# MomoinololuM3_Rev1_1.net
KiCad netlist of a schematic drawn in EAGLE
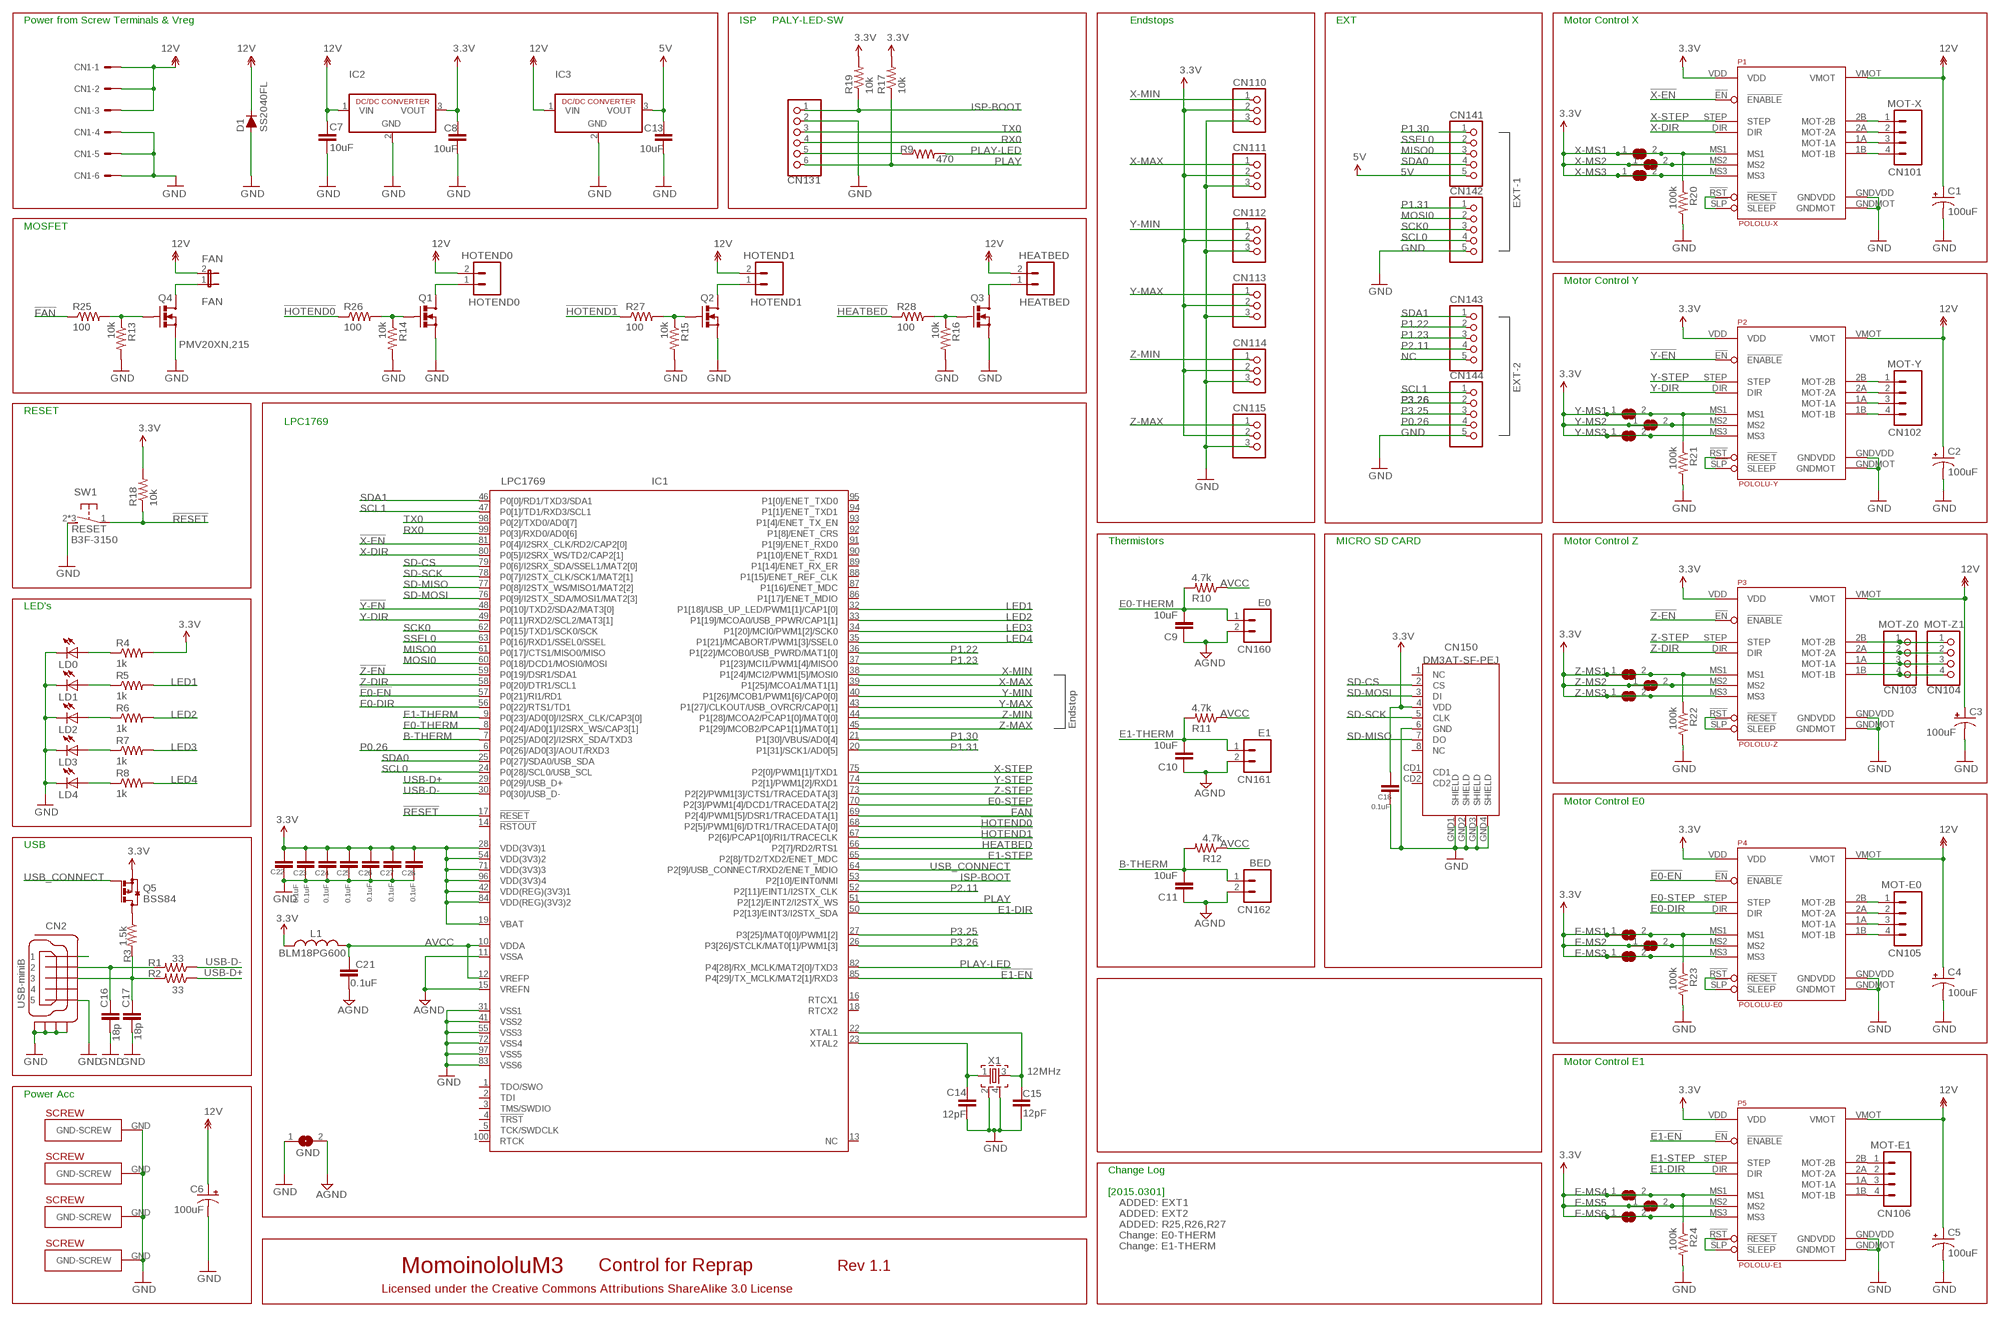
[diagram p0: schematic, sheet 1]

(export (version "E")
  (design (tool "Eeschema 10.0.6"))
  (components
    (comp (ref "C1")
      (value "100uF")
      (footprint "eagle-import:UD-6,3X7,7_NICHICON")
      (libsource (lib "eagle-import") (part "CPOL-USUD-6,3X7,7"))
    )
    (comp (ref "C2")
      (value "100uF")
      (footprint "eagle-import:UD-6,3X7,7_NICHICON")
      (libsource (lib "eagle-import") (part "CPOL-USUD-6,3X7,7"))
    )
    (comp (ref "C3")
      (value "100uF")
      (footprint "eagle-import:UD-6,3X7,7_NICHICON")
      (libsource (lib "eagle-import") (part "CPOL-USUD-6,3X7,7"))
    )
    (comp (ref "C4")
      (value "100uF")
      (footprint "eagle-import:UD-6,3X7,7_NICHICON")
      (libsource (lib "eagle-import") (part "CPOL-USUD-6,3X7,7"))
    )
    (comp (ref "C5")
      (value "100uF")
      (footprint "eagle-import:UD-6,3X7,7_NICHICON")
      (libsource (lib "eagle-import") (part "CPOL-USUD-6,3X7,7"))
    )
    (comp (ref "C6")
      (value "100uF")
      (footprint "eagle-import:UD-6,3X7,7_NICHICON")
      (libsource (lib "eagle-import") (part "CPOL-USUD-6,3X7,7"))
    )
    (comp (ref "C7")
      (value "10uF")
      (footprint "eagle-import:RCL_C1206K")
      (libsource (lib "eagle-import") (part "RCL_C-EUC1206K"))
    )
    (comp (ref "C8")
      (value "10uF")
      (footprint "eagle-import:RCL_C1206K")
      (libsource (lib "eagle-import") (part "RCL_C-EUC1206K"))
    )
    (comp (ref "C9")
      (value "10uF")
      (footprint "eagle-import:RCL_C1206K")
      (libsource (lib "eagle-import") (part "RCL_C-EUC1206K"))
    )
    (comp (ref "C10")
      (value "10uF")
      (footprint "eagle-import:RCL_C1206K")
      (libsource (lib "eagle-import") (part "RCL_C-EUC1206K"))
    )
    (comp (ref "C11")
      (value "10uF")
      (footprint "eagle-import:RCL_C1206K")
      (libsource (lib "eagle-import") (part "RCL_C-EUC1206K"))
    )
    (comp (ref "C13")
      (value "10uF")
      (footprint "eagle-import:RCL_C1206K")
      (libsource (lib "eagle-import") (part "RCL_C-EUC1206K"))
    )
    (comp (ref "C14")
      (value "12pF")
      (footprint "eagle-import:C0603")
      (libsource (lib "eagle-import") (part "C-EUC0603"))
    )
    (comp (ref "C15")
      (value "12pF")
      (footprint "eagle-import:C0603")
      (libsource (lib "eagle-import") (part "C-EUC0603"))
    )
    (comp (ref "C16")
      (value "18p")
      (footprint "eagle-import:C0603")
      (libsource (lib "eagle-import") (part "C-EUC0603"))
    )
    (comp (ref "C17")
      (value "18p")
      (footprint "eagle-import:C0603")
      (libsource (lib "eagle-import") (part "C-EUC0603"))
    )
    (comp (ref "C18")
      (value "0.1uF")
      (footprint "eagle-import:C0603")
      (libsource (lib "eagle-import") (part "C-EUC0603"))
    )
    (comp (ref "C21")
      (value "0.1uF")
      (footprint "eagle-import:C0603")
      (libsource (lib "eagle-import") (part "C-EUC0603"))
    )
    (comp (ref "C22")
      (value "0.1uF")
      (footprint "eagle-import:C0603")
      (libsource (lib "eagle-import") (part "C-EUC0603"))
    )
    (comp (ref "C23")
      (value "0.1uF")
      (footprint "eagle-import:C0603")
      (libsource (lib "eagle-import") (part "C-EUC0603"))
    )
    (comp (ref "C24")
      (value "0.1uF")
      (footprint "eagle-import:C0603")
      (libsource (lib "eagle-import") (part "C-EUC0603"))
    )
    (comp (ref "C25")
      (value "0.1uF")
      (footprint "eagle-import:C0603")
      (libsource (lib "eagle-import") (part "C-EUC0603"))
    )
    (comp (ref "C26")
      (value "0.1uF")
      (footprint "eagle-import:C0603")
      (libsource (lib "eagle-import") (part "C-EUC0603"))
    )
    (comp (ref "C27")
      (value "0.1uF")
      (footprint "eagle-import:C0603")
      (libsource (lib "eagle-import") (part "C-EUC0603"))
    )
    (comp (ref "C28")
      (value "0.1uF")
      (footprint "eagle-import:C0603")
      (libsource (lib "eagle-import") (part "C-EUC0603"))
    )
    (comp (ref "CN1")
      (value "556X-6H")
      (footprint "eagle-import:5569-6")
      (libsource (lib "eagle-import") (part "556X-6H"))
    )
    (comp (ref "CN2")
      (value "USB-miniB")
      (footprint "eagle-import:CON-HIROSE_UX60A-MB-5ST")
      (libsource (lib "eagle-import") (part "CON-HIROSE_MINI-USB-SHIELD-UX60A-MB-5ST"))
    )
    (comp (ref "CN101")
      (value "MOT-X")
      (footprint "eagle-import:SPARKFUN_MOLEX-1X4")
      (libsource (lib "eagle-import") (part "SPARKFUN_M04POLAR"))
    )
    (comp (ref "CN102")
      (value "MOT-Y")
      (footprint "eagle-import:SPARKFUN_MOLEX-1X4")
      (libsource (lib "eagle-import") (part "SPARKFUN_M04POLAR"))
    )
    (comp (ref "CN103")
      (value "MOT-Z0")
      (footprint "eagle-import:1X04")
      (libsource (lib "eagle-import") (part "PINHD-1X4"))
    )
    (comp (ref "CN104")
      (value "MOT-Z1")
      (footprint "eagle-import:1X04")
      (libsource (lib "eagle-import") (part "PINHD-1X4"))
    )
    (comp (ref "CN105")
      (value "MOT-E0")
      (footprint "eagle-import:SPARKFUN_MOLEX-1X4")
      (libsource (lib "eagle-import") (part "SPARKFUN_M04POLAR"))
    )
    (comp (ref "CN106")
      (value "MOT-E1")
      (footprint "eagle-import:SPARKFUN_MOLEX-1X4")
      (libsource (lib "eagle-import") (part "SPARKFUN_M04POLAR"))
    )
    (comp (ref "CN110")
      (value "PINHD-1X3")
      (footprint "eagle-import:1X03")
      (libsource (lib "eagle-import") (part "PINHD-1X3"))
    )
    (comp (ref "CN111")
      (value "PINHD-1X3")
      (footprint "eagle-import:1X03")
      (libsource (lib "eagle-import") (part "PINHD-1X3"))
    )
    (comp (ref "CN112")
      (value "PINHD-1X3")
      (footprint "eagle-import:1X03")
      (libsource (lib "eagle-import") (part "PINHD-1X3"))
    )
    (comp (ref "CN113")
      (value "PINHD-1X3")
      (footprint "eagle-import:1X03")
      (libsource (lib "eagle-import") (part "PINHD-1X3"))
    )
    (comp (ref "CN114")
      (value "PINHD-1X3")
      (footprint "eagle-import:1X03")
      (libsource (lib "eagle-import") (part "PINHD-1X3"))
    )
    (comp (ref "CN115")
      (value "PINHD-1X3")
      (footprint "eagle-import:1X03")
      (libsource (lib "eagle-import") (part "PINHD-1X3"))
    )
    (comp (ref "CN131")
      (value "PINHD-1X6")
      (footprint "eagle-import:1X06")
      (libsource (lib "eagle-import") (part "PINHD-1X6"))
    )
    (comp (ref "CN141")
      (value "PINHD-1X5")
      (footprint "eagle-import:1X05")
      (libsource (lib "eagle-import") (part "PINHD-1X5"))
    )
    (comp (ref "CN142")
      (value "PINHD-1X5")
      (footprint "eagle-import:1X05")
      (libsource (lib "eagle-import") (part "PINHD-1X5"))
    )
    (comp (ref "CN143")
      (value "PINHD-1X5")
      (footprint "eagle-import:1X05")
      (libsource (lib "eagle-import") (part "PINHD-1X5"))
    )
    (comp (ref "CN144")
      (value "PINHD-1X5")
      (footprint "eagle-import:1X05")
      (libsource (lib "eagle-import") (part "PINHD-1X5"))
    )
    (comp (ref "CN150")
      (value "DM3AT-SF-PEJ")
      (footprint "eagle-import:DM3AT-SF-PEJ")
      (libsource (lib "eagle-import") (part "DM3AT-SF-PEJ"))
    )
    (comp (ref "CN160")
      (value "E0")
      (footprint "eagle-import:SPARKFUN_1X02")
      (libsource (lib "eagle-import") (part "momoinololuM3_SPARKFUN_M02PTH"))
    )
    (comp (ref "CN161")
      (value "E1")
      (footprint "eagle-import:SPARKFUN_1X02")
      (libsource (lib "eagle-import") (part "momoinololuM3_SPARKFUN_M02PTH"))
    )
    (comp (ref "CN162")
      (value "BED")
      (footprint "eagle-import:SPARKFUN_1X02")
      (libsource (lib "eagle-import") (part "momoinololuM3_SPARKFUN_M02PTH"))
    )
    (comp (ref "D1")
      (value "SS2040FL")
      (footprint "eagle-import:SEMICON-SMD-IPC_SOD123")
      (libsource (lib "eagle-import") (part "SEMICON-SMD-IPC_D-FILL-SOD123"))
    )
    (comp (ref "E-MS1")
      (value "SJ")
      (footprint "eagle-import:SJ")
      (libsource (lib "eagle-import") (part "SJ"))
    )
    (comp (ref "E-MS2")
      (value "SJ")
      (footprint "eagle-import:SJ")
      (libsource (lib "eagle-import") (part "SJ"))
    )
    (comp (ref "E-MS3")
      (value "SJ")
      (footprint "eagle-import:SJ")
      (libsource (lib "eagle-import") (part "SJ"))
    )
    (comp (ref "E-MS4")
      (value "SJ")
      (footprint "eagle-import:SJ")
      (libsource (lib "eagle-import") (part "SJ"))
    )
    (comp (ref "E-MS5")
      (value "SJ")
      (footprint "eagle-import:SJ")
      (libsource (lib "eagle-import") (part "SJ"))
    )
    (comp (ref "E-MS6")
      (value "SJ")
      (footprint "eagle-import:SJ")
      (libsource (lib "eagle-import") (part "SJ"))
    )
    (comp (ref "FAN")
      (value "FAN")
      (footprint "eagle-import:SPARKFUN_1X02")
      (libsource (lib "eagle-import") (part "SPARKFUN_JUMPER-2PTH"))
    )
    (comp (ref "GND") (value "SJ") (footprint "eagle-import:SJ") (libsource (lib "eagle-import") (part "SJ")))
    (comp (ref "HEATBED")
      (value "HEATBED")
      (footprint "eagle-import:SCREWTERMINAL-5.08MM-2")
      (libsource (lib "eagle-import") (part "SPARKFUN_M025.08MM"))
    )
    (comp (ref "HOLE1")
      (value "PLATED-SCREW")
      (footprint "eagle-import:PLATEDSCREW")
      (libsource (lib "eagle-import") (part "PLATED-SCREW"))
    )
    (comp (ref "HOLE2")
      (value "PLATED-SCREW")
      (footprint "eagle-import:PLATEDSCREW")
      (libsource (lib "eagle-import") (part "PLATED-SCREW"))
    )
    (comp (ref "HOLE3")
      (value "PLATED-SCREW")
      (footprint "eagle-import:PLATEDSCREW")
      (libsource (lib "eagle-import") (part "PLATED-SCREW"))
    )
    (comp (ref "HOLE4")
      (value "PLATED-SCREW")
      (footprint "eagle-import:PLATEDSCREW")
      (libsource (lib "eagle-import") (part "PLATED-SCREW"))
    )
    (comp (ref "HOTEND0")
      (value "HOTEND0")
      (footprint "eagle-import:SCREWTERMINAL-5.08MM-2")
      (libsource (lib "eagle-import") (part "SPARKFUN_M025.08MM"))
    )
    (comp (ref "HOTEND1")
      (value "HOTEND1")
      (footprint "eagle-import:SCREWTERMINAL-5.08MM-2")
      (libsource (lib "eagle-import") (part "SPARKFUN_M025.08MM"))
    )
    (comp (ref "IC1")
      (value "LPC1769")
      (footprint "eagle-import:LQFP100-14X14")
      (libsource (lib "eagle-import") (part "LPC1768"))
    )
    (comp (ref "IC2")
      (value "R-78E3.3-0.5")
      (footprint "eagle-import:SIP3")
      (libsource (lib "eagle-import") (part "R-78C-1.03.3"))
    )
    (comp (ref "IC3")
      (value "R-78E5.0-0.5")
      (footprint "eagle-import:SIP3")
      (libsource (lib "eagle-import") (part "R-78C-1.03.3"))
    )
    (comp (ref "L1")
      (value "BLM18PG600")
      (footprint "eagle-import:L2012C")
      (libsource (lib "eagle-import") (part "L-USL2012C"))
    )
    (comp (ref "LD0")
      (value "LEDSML0805")
      (footprint "eagle-import:SML0805")
      (libsource (lib "eagle-import") (part "LEDSML0805"))
    )
    (comp (ref "LD1")
      (value "LEDSML0805")
      (footprint "eagle-import:SML0805")
      (libsource (lib "eagle-import") (part "LEDSML0805"))
    )
    (comp (ref "LD2")
      (value "LEDSML0805")
      (footprint "eagle-import:SML0805")
      (libsource (lib "eagle-import") (part "LEDSML0805"))
    )
    (comp (ref "LD3")
      (value "LEDSML0805")
      (footprint "eagle-import:SML0805")
      (libsource (lib "eagle-import") (part "LEDSML0805"))
    )
    (comp (ref "LD4")
      (value "LEDSML0805")
      (footprint "eagle-import:SML0805")
      (libsource (lib "eagle-import") (part "LEDSML0805"))
    )
    (comp (ref "P1")
      (value "POLOLU-X")
      (footprint "eagle-import:POLOLU-ALLEGRO_POLOLU-ALLEGRO-PTH")
      (libsource (lib "eagle-import") (part "POLOLU-ALLEGRO_POLOLU-ALLEGRO"))
    )
    (comp (ref "P2")
      (value "POLOLU-Y")
      (footprint "eagle-import:POLOLU-ALLEGRO_POLOLU-ALLEGRO-PTH")
      (libsource (lib "eagle-import") (part "POLOLU-ALLEGRO_POLOLU-ALLEGRO"))
    )
    (comp (ref "P3")
      (value "POLOLU-Z")
      (footprint "eagle-import:POLOLU-ALLEGRO_POLOLU-ALLEGRO-PTH")
      (libsource (lib "eagle-import") (part "POLOLU-ALLEGRO_POLOLU-ALLEGRO"))
    )
    (comp (ref "P4")
      (value "POLOLU-E0")
      (footprint "eagle-import:POLOLU-ALLEGRO_POLOLU-ALLEGRO-PTH")
      (libsource (lib "eagle-import") (part "POLOLU-ALLEGRO_POLOLU-ALLEGRO"))
    )
    (comp (ref "P5")
      (value "POLOLU-E1")
      (footprint "eagle-import:POLOLU-ALLEGRO_POLOLU-ALLEGRO-PTH")
      (libsource (lib "eagle-import") (part "POLOLU-ALLEGRO_POLOLU-ALLEGRO"))
    )
    (comp (ref "Q1")
      (value "PSMN038-100YLX")
      (footprint "eagle-import:SOT669")
      (libsource (lib "eagle-import") (part "SPARKFUN_MOSFET-NCHANNELSOT669"))
    )
    (comp (ref "Q2")
      (value "PSMN038-100YLX")
      (footprint "eagle-import:SOT669")
      (libsource (lib "eagle-import") (part "SPARKFUN_MOSFET-NCHANNELSOT669"))
    )
    (comp (ref "Q3")
      (value "PSMN038-100YLX")
      (footprint "eagle-import:SOT669")
      (libsource (lib "eagle-import") (part "SPARKFUN_MOSFET-NCHANNELSOT669"))
    )
    (comp (ref "Q4")
      (value "PMV20XN,215")
      (footprint "eagle-import:SPARKFUN_SOT23-3")
      (libsource (lib "eagle-import") (part "momoinololuM3_SPARKFUN_MOSFET-NCHANNELSMD"))
    )
    (comp (ref "Q5")
      (value "BSS84")
      (footprint "eagle-import:SOT23")
      (libsource (lib "eagle-import") (part "BSS84"))
    )
    (comp (ref "R1")
      (value "33")
      (footprint "eagle-import:R0603")
      (libsource (lib "eagle-import") (part "R-US_R0603"))
    )
    (comp (ref "R2")
      (value "33")
      (footprint "eagle-import:R0603")
      (libsource (lib "eagle-import") (part "R-US_R0603"))
    )
    (comp (ref "R3")
      (value "1.5k")
      (footprint "eagle-import:R0603")
      (libsource (lib "eagle-import") (part "R-US_R0603"))
    )
    (comp (ref "R4")
      (value "1k")
      (footprint "eagle-import:R0603")
      (libsource (lib "eagle-import") (part "R-US_R0603"))
    )
    (comp (ref "R5")
      (value "1k")
      (footprint "eagle-import:R0603")
      (libsource (lib "eagle-import") (part "R-US_R0603"))
    )
    (comp (ref "R6")
      (value "1k")
      (footprint "eagle-import:R0603")
      (libsource (lib "eagle-import") (part "R-US_R0603"))
    )
    (comp (ref "R7")
      (value "1k")
      (footprint "eagle-import:R0603")
      (libsource (lib "eagle-import") (part "R-US_R0603"))
    )
    (comp (ref "R8")
      (value "1k")
      (footprint "eagle-import:R0603")
      (libsource (lib "eagle-import") (part "R-US_R0603"))
    )
    (comp (ref "R9")
      (value "470")
      (footprint "eagle-import:R0603")
      (libsource (lib "eagle-import") (part "R-US_R0603"))
    )
    (comp (ref "R10")
      (value "4.7k")
      (footprint "eagle-import:R0603")
      (libsource (lib "eagle-import") (part "R-US_R0603"))
    )
    (comp (ref "R11")
      (value "4.7k")
      (footprint "eagle-import:R0603")
      (libsource (lib "eagle-import") (part "R-US_R0603"))
    )
    (comp (ref "R12")
      (value "4.7k")
      (footprint "eagle-import:R0603")
      (libsource (lib "eagle-import") (part "R-US_R0603"))
    )
    (comp (ref "R13")
      (value "10k")
      (footprint "eagle-import:R0603")
      (libsource (lib "eagle-import") (part "R-US_R0603"))
    )
    (comp (ref "R14")
      (value "10k")
      (footprint "eagle-import:R0603")
      (libsource (lib "eagle-import") (part "R-US_R0603"))
    )
    (comp (ref "R15")
      (value "10k")
      (footprint "eagle-import:R0603")
      (libsource (lib "eagle-import") (part "R-US_R0603"))
    )
    (comp (ref "R16")
      (value "10k")
      (footprint "eagle-import:R0603")
      (libsource (lib "eagle-import") (part "R-US_R0603"))
    )
    (comp (ref "R17")
      (value "10k")
      (footprint "eagle-import:R0603")
      (libsource (lib "eagle-import") (part "R-US_R0603"))
    )
    (comp (ref "R18")
      (value "10k")
      (footprint "eagle-import:R0603")
      (libsource (lib "eagle-import") (part "R-US_R0603"))
    )
    (comp (ref "R19")
      (value "10k")
      (footprint "eagle-import:R0603")
      (libsource (lib "eagle-import") (part "R-US_R0603"))
    )
    (comp (ref "R20")
      (value "100k")
      (footprint "eagle-import:R0603")
      (libsource (lib "eagle-import") (part "R-US_R0603"))
    )
    (comp (ref "R21")
      (value "100k")
      (footprint "eagle-import:R0603")
      (libsource (lib "eagle-import") (part "R-US_R0603"))
    )
    (comp (ref "R22")
      (value "100k")
      (footprint "eagle-import:R0603")
      (libsource (lib "eagle-import") (part "R-US_R0603"))
    )
    (comp (ref "R23")
      (value "100k")
      (footprint "eagle-import:R0603")
      (libsource (lib "eagle-import") (part "R-US_R0603"))
    )
    (comp (ref "R24")
      (value "100k")
      (footprint "eagle-import:R0603")
      (libsource (lib "eagle-import") (part "R-US_R0603"))
    )
    (comp (ref "R25")
      (value "100")
      (footprint "eagle-import:R0603")
      (libsource (lib "eagle-import") (part "R-US_R0603"))
    )
    (comp (ref "R26")
      (value "100")
      (footprint "eagle-import:R0603")
      (libsource (lib "eagle-import") (part "R-US_R0603"))
    )
    (comp (ref "R27")
      (value "100")
      (footprint "eagle-import:R0603")
      (libsource (lib "eagle-import") (part "R-US_R0603"))
    )
    (comp (ref "R28")
      (value "100")
      (footprint "eagle-import:R0603")
      (libsource (lib "eagle-import") (part "R-US_R0603"))
    )
    (comp (ref "SW1")
      (value "B3F-3150")
      (footprint "eagle-import:B3F-31XX")
      (fields (field (name "MPN") "B3F-3100"))
      (libsource (lib "eagle-import") (part "31-XX"))
    )
    (comp (ref "X-MS1")
      (value "SJ")
      (footprint "eagle-import:SJ")
      (libsource (lib "eagle-import") (part "SJ"))
    )
    (comp (ref "X-MS2")
      (value "SJ")
      (footprint "eagle-import:SJ")
      (libsource (lib "eagle-import") (part "SJ"))
    )
    (comp (ref "X-MS3")
      (value "SJ")
      (footprint "eagle-import:SJ")
      (libsource (lib "eagle-import") (part "SJ"))
    )
    (comp (ref "X1")
      (value "12MHz")
      (footprint "eagle-import:FA-238")
      (libsource (lib "eagle-import") (part "FA-238"))
    )
    (comp (ref "Y-MS1")
      (value "SJ")
      (footprint "eagle-import:SJ")
      (libsource (lib "eagle-import") (part "SJ"))
    )
    (comp (ref "Y-MS2")
      (value "SJ")
      (footprint "eagle-import:SJ")
      (libsource (lib "eagle-import") (part "SJ"))
    )
    (comp (ref "Y-MS3")
      (value "SJ")
      (footprint "eagle-import:SJ")
      (libsource (lib "eagle-import") (part "SJ"))
    )
    (comp (ref "Z-MS1")
      (value "SJ")
      (footprint "eagle-import:SJ")
      (libsource (lib "eagle-import") (part "SJ"))
    )
    (comp (ref "Z-MS2")
      (value "SJ")
      (footprint "eagle-import:SJ")
      (libsource (lib "eagle-import") (part "SJ"))
    )
    (comp (ref "Z-MS3")
      (value "SJ")
      (footprint "eagle-import:SJ")
      (libsource (lib "eagle-import") (part "SJ"))
    )
  )
  (nets
    (net (code "1") (name "/AVCC") (class "Default")
      (node (ref "C21") (pin "1") (pinfunction "1_1") (pintype "passive"))
      (node (ref "IC1") (pin "10") (pinfunction "VDDA_10") (pintype "bidirectional"))
      (node (ref "IC1") (pin "12") (pinfunction "VREFP_12") (pintype "bidirectional"))
      (node (ref "L1") (pin "2") (pinfunction "2_2") (pintype "passive"))
      (node (ref "R10") (pin "1") (pinfunction "1_1") (pintype "passive"))
      (node (ref "R11") (pin "1") (pinfunction "1_1") (pintype "passive"))
      (node (ref "R12") (pin "1") (pinfunction "1_1") (pintype "passive"))
    )
    (net (code "2") (name "/B-THERM") (class "Default")
      (node (ref "C11") (pin "2") (pinfunction "2_2") (pintype "passive"))
      (node (ref "CN162") (pin "1") (pinfunction "1_1") (pintype "passive"))
      (node (ref "IC1") (pin "7") (pinfunction "P0[25]/AD0[2]/I2SRX_SDA/TXD3_7") (pintype "bidirectional"))
      (node (ref "R12") (pin "2") (pinfunction "2_2") (pintype "passive"))
    )
    (net (code "3") (name "/E0-DIR") (class "Default")
      (node (ref "IC1") (pin "56") (pinfunction "P0[22]/RTS1/TD1_56") (pintype "bidirectional"))
      (node (ref "P4") (pin "DIR") (pinfunction "DIR_DIR") (pintype "bidirectional"))
    )
    (net (code "4") (name "/E0-STEP") (class "Default")
      (node (ref "IC1") (pin "70") (pinfunction "P2[3]/PWM1[4]/DCD1/TRACEDATA[2]_70") (pintype "bidirectional"))
      (node (ref "P4") (pin "STEP") (pinfunction "STEP_STEP") (pintype "bidirectional"))
    )
    (net (code "5") (name "/E0-THERM") (class "Default")
      (node (ref "C9") (pin "2") (pinfunction "2_2") (pintype "passive"))
      (node (ref "CN160") (pin "1") (pinfunction "1_1") (pintype "passive"))
      (node (ref "IC1") (pin "8") (pinfunction "P0[24]/AD0[1]/I2SRX_WS/CAP3[1]_8") (pintype "bidirectional"))
      (node (ref "R10") (pin "2") (pinfunction "2_2") (pintype "passive"))
    )
    (net (code "6") (name "/E1-DIR") (class "Default")
      (node (ref "IC1") (pin "50") (pinfunction "P2[13]/EINT3/I2STX_SDA_50") (pintype "bidirectional"))
      (node (ref "P5") (pin "DIR") (pinfunction "DIR_DIR") (pintype "bidirectional"))
    )
    (net (code "7") (name "/E1-STEP") (class "Default")
      (node (ref "IC1") (pin "65") (pinfunction "P2[8]/TD2/TXD2/ENET_MDC_65") (pintype "bidirectional"))
      (node (ref "P5") (pin "STEP") (pinfunction "STEP_STEP") (pintype "bidirectional"))
    )
    (net (code "8") (name "/E1-THERM") (class "Default")
      (node (ref "C10") (pin "2") (pinfunction "2_2") (pintype "passive"))
      (node (ref "CN161") (pin "1") (pinfunction "1_1") (pintype "passive"))
      (node (ref "IC1") (pin "9") (pinfunction "P0[23]/AD0[0]/I2SRX_CLK/CAP3[0]_9") (pintype "bidirectional"))
      (node (ref "R11") (pin "2") (pinfunction "2_2") (pintype "passive"))
    )
    (net (code "9") (name "/ISP-BOOT") (class "Default")
      (node (ref "CN131") (pin "1") (pinfunction "1_1") (pintype "passive"))
      (node (ref "IC1") (pin "53") (pinfunction "P2[10]/EINT0/NMI_53") (pintype "bidirectional"))
      (node (ref "R19") (pin "1") (pinfunction "1_1") (pintype "passive"))
    )
    (net (code "10") (name "/LED1") (class "Default")
      (node (ref "IC1") (pin "32") (pinfunction "P1[18]/USB_UP_LED/PWM1[1]/CAP1[0]_32") (pintype "bidirectional"))
      (node (ref "R5") (pin "2") (pinfunction "2_2") (pintype "passive"))
    )
    (net (code "11") (name "/LED2") (class "Default")
      (node (ref "IC1") (pin "33") (pinfunction "P1[19]/MCOA0/USB_PPWR/CAP1[1]_33") (pintype "bidirectional"))
      (node (ref "R6") (pin "2") (pinfunction "2_2") (pintype "passive"))
    )
    (net (code "12") (name "/LED3") (class "Default")
      (node (ref "IC1") (pin "34") (pinfunction "P1[20]/MCI0/PWM1[2]/SCK0_34") (pintype "bidirectional"))
      (node (ref "R7") (pin "2") (pinfunction "2_2") (pintype "passive"))
    )
    (net (code "13") (name "/LED4") (class "Default")
      (node (ref "IC1") (pin "35") (pinfunction "P1[21]/MCABORT/PWM1[3]/SSEL0_35") (pintype "bidirectional"))
      (node (ref "R8") (pin "2") (pinfunction "2_2") (pintype "passive"))
    )
    (net (code "14") (name "/MISO0") (class "Default")
      (node (ref "CN141") (pin "3") (pinfunction "3_3") (pintype "passive"))
      (node (ref "IC1") (pin "61") (pinfunction "P0[17]/CTS1/MISO0/MISO_61") (pintype "bidirectional"))
    )
    (net (code "15") (name "/MOSI0") (class "Default")
      (node (ref "CN142") (pin "2") (pinfunction "2_2") (pintype "passive"))
      (node (ref "IC1") (pin "60") (pinfunction "P0[18]/DCD1/MOSI0/MOSI_60") (pintype "bidirectional"))
    )
    (net (code "16") (name "/NC") (class "Default")
      (node (ref "CN143") (pin "5") (pinfunction "5_5") (pintype "passive"))
    )
    (net (code "17") (name "/P0.26") (class "Default")
      (node (ref "CN144") (pin "4") (pinfunction "4_4") (pintype "passive"))
      (node (ref "IC1") (pin "6") (pinfunction "P0[26]/AD0[3]/AOUT/RXD3_6") (pintype "bidirectional"))
    )
    (net (code "18") (name "/P1.22") (class "Default")
      (node (ref "CN143") (pin "2") (pinfunction "2_2") (pintype "passive"))
      (node (ref "IC1") (pin "36") (pinfunction "P1[22]/MCOB0/USB_PWRD/MAT1[0]_36") (pintype "bidirectional"))
    )
    (net (code "19") (name "/P1.23") (class "Default")
      (node (ref "CN143") (pin "3") (pinfunction "3_3") (pintype "passive"))
      (node (ref "IC1") (pin "37") (pinfunction "P1[23]/MCI1/PWM1[4]/MISO0_37") (pintype "bidirectional"))
    )
    (net (code "20") (name "/P1.30") (class "Default")
      (node (ref "CN141") (pin "1") (pinfunction "1_1") (pintype "passive"))
      (node (ref "IC1") (pin "21") (pinfunction "P1[30]/VBUS/AD0[4]_21") (pintype "bidirectional"))
    )
    (net (code "21") (name "/P1.31") (class "Default")
      (node (ref "CN142") (pin "1") (pinfunction "1_1") (pintype "passive"))
      (node (ref "IC1") (pin "20") (pinfunction "P1[31]/SCK1/AD0[5]_20") (pintype "bidirectional"))
    )
    (net (code "22") (name "/P2.11") (class "Default")
      (node (ref "CN143") (pin "4") (pinfunction "4_4") (pintype "passive"))
      (node (ref "IC1") (pin "52") (pinfunction "P2[11]/EINT1/I2STX_CLK_52") (pintype "bidirectional"))
    )
    (net (code "23") (name "/P3.25") (class "Default")
      (node (ref "CN144") (pin "3") (pinfunction "3_3") (pintype "passive"))
      (node (ref "IC1") (pin "27") (pinfunction "P3[25]/MAT0[0]/PWM1[2]_27") (pintype "bidirectional"))
    )
    (net (code "24") (name "/P3.26") (class "Default")
      (node (ref "CN144") (pin "2") (pinfunction "2_2") (pintype "passive"))
      (node (ref "IC1") (pin "26") (pinfunction "P3[26]/STCLK/MAT0[1]/PWM1[3]_26") (pintype "bidirectional"))
    )
    (net (code "25") (name "/PLAY") (class "Default")
      (node (ref "CN131") (pin "6") (pinfunction "6_6") (pintype "passive"))
      (node (ref "IC1") (pin "51") (pinfunction "P2[12]/EINT2/I2STX_WS_51") (pintype "bidirectional"))
      (node (ref "R17") (pin "1") (pinfunction "1_1") (pintype "passive"))
    )
    (net (code "26") (name "/PLAY-LED") (class "Default")
      (node (ref "IC1") (pin "82") (pinfunction "P4[28]/RX_MCLK/MAT2[0]/TXD3_82") (pintype "bidirectional"))
      (node (ref "R9") (pin "2") (pinfunction "2_2") (pintype "passive"))
    )
    (net (code "27") (name "/RX0") (class "Default")
      (node (ref "CN131") (pin "4") (pinfunction "4_4") (pintype "passive"))
      (node (ref "IC1") (pin "99") (pinfunction "P0[3]/RXD0/AD0[6]_99") (pintype "bidirectional"))
    )
    (net (code "28") (name "/SCK0") (class "Default")
      (node (ref "CN142") (pin "3") (pinfunction "3_3") (pintype "passive"))
      (node (ref "IC1") (pin "62") (pinfunction "P0[15]/TXD1/SCK0/SCK_62") (pintype "bidirectional"))
    )
    (net (code "29") (name "/SCL0") (class "Default")
      (node (ref "CN142") (pin "4") (pinfunction "4_4") (pintype "passive"))
      (node (ref "IC1") (pin "24") (pinfunction "P0[28]/SCL0/USB_SCL_24") (pintype "bidirectional"))
    )
    (net (code "30") (name "/SCL1") (class "Default")
      (node (ref "CN144") (pin "1") (pinfunction "1_1") (pintype "passive"))
      (node (ref "IC1") (pin "47") (pinfunction "P0[1]/TD1/RXD3/SCL1_47") (pintype "bidirectional"))
    )
    (net (code "31") (name "/SD-CS") (class "Default")
      (node (ref "CN150") (pin "2") (pinfunction "CS_2") (pintype "bidirectional"))
      (node (ref "IC1") (pin "79") (pinfunction "P0[6]/I2SRX_SDA/SSEL1/MAT2[0]_79") (pintype "bidirectional"))
    )
    (net (code "32") (name "/SD-MISO") (class "Default")
      (node (ref "CN150") (pin "7") (pinfunction "DO_7") (pintype "bidirectional"))
      (node (ref "IC1") (pin "77") (pinfunction "P0[8]/I2STX_WS/MISO1/MAT2[2]_77") (pintype "bidirectional"))
    )
    (net (code "33") (name "/SD-MOSI") (class "Default")
      (node (ref "CN150") (pin "3") (pinfunction "DI_3") (pintype "bidirectional"))
      (node (ref "IC1") (pin "76") (pinfunction "P0[9]/I2STX_SDA/MOSI1/MAT2[3]_76") (pintype "bidirectional"))
    )
    (net (code "34") (name "/SD-SCK") (class "Default")
      (node (ref "CN150") (pin "5") (pinfunction "CLK_5") (pintype "bidirectional"))
      (node (ref "IC1") (pin "78") (pinfunction "P0[7]/I2STX_CLK/SCK1/MAT2[1]_78") (pintype "bidirectional"))
    )
    (net (code "35") (name "/SDA0") (class "Default")
      (node (ref "CN141") (pin "4") (pinfunction "4_4") (pintype "passive"))
      (node (ref "IC1") (pin "25") (pinfunction "P0[27]/SDA0/USB_SDA_25") (pintype "bidirectional"))
    )
    (net (code "36") (name "/SDA1") (class "Default")
      (node (ref "CN143") (pin "1") (pinfunction "1_1") (pintype "passive"))
      (node (ref "IC1") (pin "46") (pinfunction "P0[0]/RD1/TXD3/SDA1_46") (pintype "bidirectional"))
    )
    (net (code "37") (name "/SSEL0") (class "Default")
      (node (ref "CN141") (pin "2") (pinfunction "2_2") (pintype "passive"))
      (node (ref "IC1") (pin "63") (pinfunction "P0[16]/RXD1/SSEL0/SSEL_63") (pintype "bidirectional"))
    )
    (net (code "38") (name "/TX0") (class "Default")
      (node (ref "CN131") (pin "3") (pinfunction "3_3") (pintype "passive"))
      (node (ref "IC1") (pin "98") (pinfunction "P0[2]/TXD0/AD0[7]_98") (pintype "bidirectional"))
    )
    (net (code "39") (name "/USB-D+") (class "Default")
      (node (ref "IC1") (pin "29") (pinfunction "P0[29]/USB_D+_29") (pintype "bidirectional"))
      (node (ref "R2") (pin "1") (pinfunction "1_1") (pintype "passive"))
    )
    (net (code "40") (name "/USB-D-") (class "Default")
      (node (ref "IC1") (pin "30") (pinfunction "P0[30]/USB_D-_30") (pintype "bidirectional"))
      (node (ref "R1") (pin "1") (pinfunction "1_1") (pintype "passive"))
    )
    (net (code "41") (name "/USB_CONNECT") (class "Default")
      (node (ref "IC1") (pin "64") (pinfunction "P2[9]/USB_CONNECT/RXD2/ENET_MDIO_64") (pintype "bidirectional"))
      (node (ref "Q5") (pin "1") (pinfunction "G_1") (pintype "passive"))
    )
    (net (code "42") (name "/X-DIR") (class "Default")
      (node (ref "IC1") (pin "80") (pinfunction "P0[5]/I2SRX_WS/TD2/CAP2[1]_80") (pintype "bidirectional"))
      (node (ref "P1") (pin "DIR") (pinfunction "DIR_DIR") (pintype "bidirectional"))
    )
    (net (code "43") (name "/X-MAX") (class "Default")
      (node (ref "CN111") (pin "1") (pinfunction "1_1") (pintype "passive"))
      (node (ref "IC1") (pin "39") (pinfunction "P1[25]/MCOA1/MAT1[1]_39") (pintype "bidirectional"))
    )
    (net (code "44") (name "/X-MIN") (class "Default")
      (node (ref "CN110") (pin "1") (pinfunction "1_1") (pintype "passive"))
      (node (ref "IC1") (pin "38") (pinfunction "P1[24]/MCI2/PWM1[5]/MOSI0_38") (pintype "bidirectional"))
    )
    (net (code "45") (name "/X-STEP") (class "Default")
      (node (ref "IC1") (pin "75") (pinfunction "P2[0]/PWM1[1]/TXD1_75") (pintype "bidirectional"))
      (node (ref "P1") (pin "STEP") (pinfunction "STEP_STEP") (pintype "bidirectional"))
    )
    (net (code "46") (name "/Y-DIR") (class "Default")
      (node (ref "IC1") (pin "49") (pinfunction "P0[11]/RXD2/SCL2/MAT3[1]_49") (pintype "bidirectional"))
      (node (ref "P2") (pin "DIR") (pinfunction "DIR_DIR") (pintype "bidirectional"))
    )
    (net (code "47") (name "/Y-MAX") (class "Default")
      (node (ref "CN113") (pin "1") (pinfunction "1_1") (pintype "passive"))
      (node (ref "IC1") (pin "43") (pinfunction "P1[27]/CLKOUT/USB_OVRCR/CAP0[1]_43") (pintype "bidirectional"))
    )
    (net (code "48") (name "/Y-MIN") (class "Default")
      (node (ref "CN112") (pin "1") (pinfunction "1_1") (pintype "passive"))
      (node (ref "IC1") (pin "40") (pinfunction "P1[26]/MCOB1/PWM1[6]/CAP0[0]_40") (pintype "bidirectional"))
    )
    (net (code "49") (name "/Y-STEP") (class "Default")
      (node (ref "IC1") (pin "74") (pinfunction "P2[1]/PWM1[2]/RXD1_74") (pintype "bidirectional"))
      (node (ref "P2") (pin "STEP") (pinfunction "STEP_STEP") (pintype "bidirectional"))
    )
    (net (code "50") (name "/Z-DIR") (class "Default")
      (node (ref "IC1") (pin "58") (pinfunction "P0[20]/DTR1/SCL1_58") (pintype "bidirectional"))
      (node (ref "P3") (pin "DIR") (pinfunction "DIR_DIR") (pintype "bidirectional"))
    )
    (net (code "51") (name "/Z-MAX") (class "Default")
      (node (ref "CN115") (pin "1") (pinfunction "1_1") (pintype "passive"))
      (node (ref "IC1") (pin "45") (pinfunction "P1[29]/MCOB2/PCAP1[1]/MAT0[1]_45") (pintype "bidirectional"))
    )
    (net (code "52") (name "/Z-MIN") (class "Default")
      (node (ref "CN114") (pin "1") (pinfunction "1_1") (pintype "passive"))
      (node (ref "IC1") (pin "44") (pinfunction "P1[28]/MCOA2/PCAP1[0]/MAT0[0]_44") (pintype "bidirectional"))
    )
    (net (code "53") (name "/Z-STEP") (class "Default")
      (node (ref "IC1") (pin "73") (pinfunction "P2[2]/PWM1[3]/CTS1/TRACEDATA[3]_73") (pintype "bidirectional"))
      (node (ref "P3") (pin "STEP") (pinfunction "STEP_STEP") (pintype "bidirectional"))
    )
    (net (code "54") (name "/~{E0-EN}") (class "Default")
      (node (ref "IC1") (pin "57") (pinfunction "P0[21]/RI1/RD1_57") (pintype "bidirectional"))
      (node (ref "P4") (pin "!EN") (pinfunction "~{ENABLE}_!EN") (pintype "input"))
    )
    (net (code "55") (name "/~{E1-EN}") (class "Default")
      (node (ref "IC1") (pin "85") (pinfunction "P4[29]/TX_MCLK/MAT2[1]/RXD3_85") (pintype "bidirectional"))
      (node (ref "P5") (pin "!EN") (pinfunction "~{ENABLE}_!EN") (pintype "input"))
    )
    (net (code "56") (name "/~{FAN}") (class "Default")
      (node (ref "IC1") (pin "69") (pinfunction "P2[4]/PWM1[5]/DSR1/TRACEDATA[1]_69") (pintype "bidirectional"))
      (node (ref "R25") (pin "1") (pinfunction "1_1") (pintype "passive"))
    )
    (net (code "57") (name "/~{HEATBED}") (class "Default")
      (node (ref "IC1") (pin "66") (pinfunction "P2[7]/RD2/RTS1_66") (pintype "bidirectional"))
      (node (ref "R28") (pin "1") (pinfunction "1_1") (pintype "passive"))
    )
    (net (code "58") (name "/~{HOTEND0}") (class "Default")
      (node (ref "IC1") (pin "68") (pinfunction "P2[5]/PWM1[6]/DTR1/TRACEDATA[0]_68") (pintype "bidirectional"))
      (node (ref "R26") (pin "1") (pinfunction "1_1") (pintype "passive"))
    )
    (net (code "59") (name "/~{HOTEND1}") (class "Default")
      (node (ref "IC1") (pin "67") (pinfunction "P2[6]/PCAP1[0]/RI1/TRACECLK_67") (pintype "bidirectional"))
      (node (ref "R27") (pin "1") (pinfunction "1_1") (pintype "passive"))
    )
    (net (code "60") (name "/~{RESET}") (class "Default")
      (node (ref "IC1") (pin "17") (pinfunction "~{RESET}_17") (pintype "bidirectional"))
      (node (ref "R18") (pin "1") (pinfunction "1_1") (pintype "passive"))
      (node (ref "SW1") (pin "1") (pinfunction "P_1") (pintype "passive"))
    )
    (net (code "61") (name "/~{X-EN}") (class "Default")
      (node (ref "IC1") (pin "81") (pinfunction "P0[4]/I2SRX_CLK/RD2/CAP2[0]_81") (pintype "bidirectional"))
      (node (ref "P1") (pin "!EN") (pinfunction "~{ENABLE}_!EN") (pintype "input"))
    )
    (net (code "62") (name "/~{Y-EN}") (class "Default")
      (node (ref "IC1") (pin "48") (pinfunction "P0[10]/TXD2/SDA2/MAT3[0]_48") (pintype "bidirectional"))
      (node (ref "P2") (pin "!EN") (pinfunction "~{ENABLE}_!EN") (pintype "input"))
    )
    (net (code "63") (name "/~{Z-EN}") (class "Default")
      (node (ref "IC1") (pin "59") (pinfunction "P0[19]/DSR1/SDA1_59") (pintype "bidirectional"))
      (node (ref "P3") (pin "!EN") (pinfunction "~{ENABLE}_!EN") (pintype "input"))
    )
    (net (code "64") (name "3.3V") (class "Default")
      (node (ref "C18") (pin "2") (pinfunction "2_2") (pintype "passive"))
      (node (ref "C22") (pin "2") (pinfunction "2_2") (pintype "passive"))
      (node (ref "C23") (pin "2") (pinfunction "2_2") (pintype "passive"))
      (node (ref "C24") (pin "2") (pinfunction "2_2") (pintype "passive"))
      (node (ref "C25") (pin "2") (pinfunction "2_2") (pintype "passive"))
      (node (ref "C26") (pin "2") (pinfunction "2_2") (pintype "passive"))
      (node (ref "C27") (pin "2") (pinfunction "2_2") (pintype "passive"))
      (node (ref "C28") (pin "2") (pinfunction "2_2") (pintype "passive"))
      (node (ref "C8") (pin "1") (pinfunction "1_1") (pintype "passive"))
      (node (ref "CN110") (pin "2") (pinfunction "2_2") (pintype "passive"))
      (node (ref "CN111") (pin "2") (pinfunction "2_2") (pintype "passive"))
      (node (ref "CN112") (pin "2") (pinfunction "2_2") (pintype "passive"))
      (node (ref "CN113") (pin "2") (pinfunction "2_2") (pintype "passive"))
      (node (ref "CN114") (pin "2") (pinfunction "2_2") (pintype "passive"))
      (node (ref "CN115") (pin "2") (pinfunction "2_2") (pintype "passive"))
      (node (ref "CN150") (pin "4") (pinfunction "VDD_4") (pintype "bidirectional"))
      (node (ref "E-MS1") (pin "1") (pinfunction "1_1") (pintype "passive"))
      (node (ref "E-MS1") (pin "2") (pinfunction "2_2") (pintype "passive"))
      (node (ref "E-MS2") (pin "1") (pinfunction "1_1") (pintype "passive"))
      (node (ref "E-MS2") (pin "2") (pinfunction "2_2") (pintype "passive"))
      (node (ref "E-MS3") (pin "1") (pinfunction "1_1") (pintype "passive"))
      (node (ref "E-MS3") (pin "2") (pinfunction "2_2") (pintype "passive"))
      (node (ref "E-MS4") (pin "1") (pinfunction "1_1") (pintype "passive"))
      (node (ref "E-MS4") (pin "2") (pinfunction "2_2") (pintype "passive"))
      (node (ref "E-MS5") (pin "1") (pinfunction "1_1") (pintype "passive"))
      (node (ref "E-MS5") (pin "2") (pinfunction "2_2") (pintype "passive"))
      (node (ref "E-MS6") (pin "1") (pinfunction "1_1") (pintype "passive"))
      (node (ref "E-MS6") (pin "2") (pinfunction "2_2") (pintype "passive"))
      (node (ref "IC1") (pin "19") (pinfunction "VBAT_19") (pintype "bidirectional"))
      (node (ref "IC1") (pin "28") (pinfunction "VDD(3V3)1_28") (pintype "bidirectional"))
      (node (ref "IC1") (pin "42") (pinfunction "VDD(REG)(3V3)1_42") (pintype "bidirectional"))
      (node (ref "IC1") (pin "54") (pinfunction "VDD(3V3)2_54") (pintype "bidirectional"))
      (node (ref "IC1") (pin "71") (pinfunction "VDD(3V3)3_71") (pintype "bidirectional"))
      (node (ref "IC1") (pin "84") (pinfunction "VDD(REG)(3V3)2_84") (pintype "bidirectional"))
      (node (ref "IC1") (pin "96") (pinfunction "VDD(3V3)4_96") (pintype "bidirectional"))
      (node (ref "IC2") (pin "3") (pinfunction "VOUT_3") (pintype "passive"))
      (node (ref "L1") (pin "1") (pinfunction "1_1") (pintype "passive"))
      (node (ref "P1") (pin "MS1") (pinfunction "MS1_MS1") (pintype "input"))
      (node (ref "P1") (pin "MS2") (pinfunction "MS2_MS2") (pintype "input"))
      (node (ref "P1") (pin "MS3") (pinfunction "MS3_MS3") (pintype "input"))
      (node (ref "P1") (pin "VDD") (pinfunction "VDD_VDD") (pintype "power_in"))
      (node (ref "P2") (pin "MS1") (pinfunction "MS1_MS1") (pintype "input"))
      (node (ref "P2") (pin "MS2") (pinfunction "MS2_MS2") (pintype "input"))
      (node (ref "P2") (pin "MS3") (pinfunction "MS3_MS3") (pintype "input"))
      (node (ref "P2") (pin "VDD") (pinfunction "VDD_VDD") (pintype "power_in"))
      (node (ref "P3") (pin "MS1") (pinfunction "MS1_MS1") (pintype "input"))
      (node (ref "P3") (pin "MS2") (pinfunction "MS2_MS2") (pintype "input"))
      (node (ref "P3") (pin "MS3") (pinfunction "MS3_MS3") (pintype "input"))
      (node (ref "P3") (pin "VDD") (pinfunction "VDD_VDD") (pintype "power_in"))
      (node (ref "P4") (pin "MS1") (pinfunction "MS1_MS1") (pintype "input"))
      (node (ref "P4") (pin "MS2") (pinfunction "MS2_MS2") (pintype "input"))
      (node (ref "P4") (pin "MS3") (pinfunction "MS3_MS3") (pintype "input"))
      (node (ref "P4") (pin "VDD") (pinfunction "VDD_VDD") (pintype "power_in"))
      (node (ref "P5") (pin "MS1") (pinfunction "MS1_MS1") (pintype "input"))
      (node (ref "P5") (pin "MS2") (pinfunction "MS2_MS2") (pintype "input"))
      (node (ref "P5") (pin "MS3") (pinfunction "MS3_MS3") (pintype "input"))
      (node (ref "P5") (pin "VDD") (pinfunction "VDD_VDD") (pintype "power_in"))
      (node (ref "Q5") (pin "2") (pinfunction "S_2") (pintype "passive"))
      (node (ref "R17") (pin "2") (pinfunction "2_2") (pintype "passive"))
      (node (ref "R18") (pin "2") (pinfunction "2_2") (pintype "passive"))
      (node (ref "R19") (pin "2") (pinfunction "2_2") (pintype "passive"))
      (node (ref "R20") (pin "1") (pinfunction "1_1") (pintype "passive"))
      (node (ref "R21") (pin "1") (pinfunction "1_1") (pintype "passive"))
      (node (ref "R22") (pin "1") (pinfunction "1_1") (pintype "passive"))
      (node (ref "R23") (pin "1") (pinfunction "1_1") (pintype "passive"))
      (node (ref "R24") (pin "1") (pinfunction "1_1") (pintype "passive"))
      (node (ref "R4") (pin "2") (pinfunction "2_2") (pintype "passive"))
      (node (ref "X-MS1") (pin "1") (pinfunction "1_1") (pintype "passive"))
      (node (ref "X-MS1") (pin "2") (pinfunction "2_2") (pintype "passive"))
      (node (ref "X-MS2") (pin "1") (pinfunction "1_1") (pintype "passive"))
      (node (ref "X-MS2") (pin "2") (pinfunction "2_2") (pintype "passive"))
      (node (ref "X-MS3") (pin "1") (pinfunction "1_1") (pintype "passive"))
      (node (ref "X-MS3") (pin "2") (pinfunction "2_2") (pintype "passive"))
      (node (ref "Y-MS1") (pin "1") (pinfunction "1_1") (pintype "passive"))
      (node (ref "Y-MS1") (pin "2") (pinfunction "2_2") (pintype "passive"))
      (node (ref "Y-MS2") (pin "1") (pinfunction "1_1") (pintype "passive"))
      (node (ref "Y-MS2") (pin "2") (pinfunction "2_2") (pintype "passive"))
      (node (ref "Y-MS3") (pin "1") (pinfunction "1_1") (pintype "passive"))
      (node (ref "Y-MS3") (pin "2") (pinfunction "2_2") (pintype "passive"))
      (node (ref "Z-MS1") (pin "1") (pinfunction "1_1") (pintype "passive"))
      (node (ref "Z-MS1") (pin "2") (pinfunction "2_2") (pintype "passive"))
      (node (ref "Z-MS2") (pin "1") (pinfunction "1_1") (pintype "passive"))
      (node (ref "Z-MS2") (pin "2") (pinfunction "2_2") (pintype "passive"))
      (node (ref "Z-MS3") (pin "1") (pinfunction "1_1") (pintype "passive"))
      (node (ref "Z-MS3") (pin "2") (pinfunction "2_2") (pintype "passive"))
    )
    (net (code "65") (name "5V") (class "Default")
      (node (ref "C13") (pin "1") (pinfunction "1_1") (pintype "passive"))
      (node (ref "CN141") (pin "5") (pinfunction "5_5") (pintype "passive"))
      (node (ref "IC3") (pin "3") (pinfunction "VOUT_3") (pintype "passive"))
    )
    (net (code "66") (name "12V") (class "Default")
      (node (ref "C1") (pin "+") (pinfunction "+_+") (pintype "passive"))
      (node (ref "C2") (pin "+") (pinfunction "+_+") (pintype "passive"))
      (node (ref "C3") (pin "+") (pinfunction "+_+") (pintype "passive"))
      (node (ref "C4") (pin "+") (pinfunction "+_+") (pintype "passive"))
      (node (ref "C5") (pin "+") (pinfunction "+_+") (pintype "passive"))
      (node (ref "C6") (pin "+") (pinfunction "+_+") (pintype "passive"))
      (node (ref "C7") (pin "1") (pinfunction "1_1") (pintype "passive"))
      (node (ref "CN1") (pin "1") (pinfunction "S_1") (pintype "passive"))
      (node (ref "CN1") (pin "2") (pinfunction "S_2") (pintype "passive"))
      (node (ref "CN1") (pin "3") (pinfunction "S_3") (pintype "passive"))
      (node (ref "D1") (pin "1") (pinfunction "C_1") (pintype "passive"))
      (node (ref "FAN") (pin "2") (pinfunction "2_2") (pintype "passive"))
      (node (ref "HEATBED") (pin "2") (pinfunction "2_2") (pintype "passive"))
      (node (ref "HOTEND0") (pin "2") (pinfunction "2_2") (pintype "passive"))
      (node (ref "HOTEND1") (pin "2") (pinfunction "2_2") (pintype "passive"))
      (node (ref "IC2") (pin "1") (pinfunction "VIN_1") (pintype "passive"))
      (node (ref "IC3") (pin "1") (pinfunction "VIN_1") (pintype "passive"))
      (node (ref "P1") (pin "VMOT") (pinfunction "VMOT_VMOT") (pintype "power_in"))
      (node (ref "P2") (pin "VMOT") (pinfunction "VMOT_VMOT") (pintype "power_in"))
      (node (ref "P3") (pin "VMOT") (pinfunction "VMOT_VMOT") (pintype "power_in"))
      (node (ref "P4") (pin "VMOT") (pinfunction "VMOT_VMOT") (pintype "power_in"))
      (node (ref "P5") (pin "VMOT") (pinfunction "VMOT_VMOT") (pintype "power_in"))
    )
    (net (code "67") (name "AGND") (class "Default")
      (node (ref "C10") (pin "1") (pinfunction "1_1") (pintype "passive"))
      (node (ref "C11") (pin "1") (pinfunction "1_1") (pintype "passive"))
      (node (ref "C21") (pin "2") (pinfunction "2_2") (pintype "passive"))
      (node (ref "C9") (pin "1") (pinfunction "1_1") (pintype "passive"))
      (node (ref "CN160") (pin "2") (pinfunction "2_2") (pintype "passive"))
      (node (ref "CN161") (pin "2") (pinfunction "2_2") (pintype "passive"))
      (node (ref "CN162") (pin "2") (pinfunction "2_2") (pintype "passive"))
      (node (ref "GND") (pin "2") (pinfunction "2_2") (pintype "passive"))
      (node (ref "IC1") (pin "11") (pinfunction "VSSA_11") (pintype "bidirectional"))
      (node (ref "IC1") (pin "15") (pinfunction "VREFN_15") (pintype "bidirectional"))
    )
    (net (code "68") (name "GND") (class "Default")
      (node (ref "C1") (pin "-") (pinfunction "-_-") (pintype "passive"))
      (node (ref "C13") (pin "2") (pinfunction "2_2") (pintype "passive"))
      (node (ref "C14") (pin "2") (pinfunction "2_2") (pintype "passive"))
      (node (ref "C15") (pin "2") (pinfunction "2_2") (pintype "passive"))
      (node (ref "C16") (pin "2") (pinfunction "2_2") (pintype "passive"))
      (node (ref "C17") (pin "2") (pinfunction "2_2") (pintype "passive"))
      (node (ref "C18") (pin "1") (pinfunction "1_1") (pintype "passive"))
      (node (ref "C2") (pin "-") (pinfunction "-_-") (pintype "passive"))
      (node (ref "C22") (pin "1") (pinfunction "1_1") (pintype "passive"))
      (node (ref "C23") (pin "1") (pinfunction "1_1") (pintype "passive"))
      (node (ref "C24") (pin "1") (pinfunction "1_1") (pintype "passive"))
      (node (ref "C25") (pin "1") (pinfunction "1_1") (pintype "passive"))
      (node (ref "C26") (pin "1") (pinfunction "1_1") (pintype "passive"))
      (node (ref "C27") (pin "1") (pinfunction "1_1") (pintype "passive"))
      (node (ref "C28") (pin "1") (pinfunction "1_1") (pintype "passive"))
      (node (ref "C3") (pin "-") (pinfunction "-_-") (pintype "passive"))
      (node (ref "C4") (pin "-") (pinfunction "-_-") (pintype "passive"))
      (node (ref "C5") (pin "-") (pinfunction "-_-") (pintype "passive"))
      (node (ref "C6") (pin "-") (pinfunction "-_-") (pintype "passive"))
      (node (ref "C7") (pin "2") (pinfunction "2_2") (pintype "passive"))
      (node (ref "C8") (pin "2") (pinfunction "2_2") (pintype "passive"))
      (node (ref "CN1") (pin "4") (pinfunction "S_4") (pintype "passive"))
      (node (ref "CN1") (pin "5") (pinfunction "S_5") (pintype "passive"))
      (node (ref "CN1") (pin "6") (pinfunction "S_6") (pintype "passive"))
      (node (ref "CN110") (pin "3") (pinfunction "3_3") (pintype "passive"))
      (node (ref "CN111") (pin "3") (pinfunction "3_3") (pintype "passive"))
      (node (ref "CN112") (pin "3") (pinfunction "3_3") (pintype "passive"))
      (node (ref "CN113") (pin "3") (pinfunction "3_3") (pintype "passive"))
      (node (ref "CN114") (pin "3") (pinfunction "3_3") (pintype "passive"))
      (node (ref "CN115") (pin "3") (pinfunction "3_3") (pintype "passive"))
      (node (ref "CN131") (pin "2") (pinfunction "2_2") (pintype "passive"))
      (node (ref "CN142") (pin "5") (pinfunction "5_5") (pintype "passive"))
      (node (ref "CN144") (pin "5") (pinfunction "5_5") (pintype "passive"))
      (node (ref "CN150") (pin "6") (pinfunction "GND_6") (pintype "bidirectional"))
      (node (ref "CN150") (pin "GND1") (pinfunction "SHIELD_GND1") (pintype "bidirectional"))
      (node (ref "CN150") (pin "GND2") (pinfunction "SHIELD_GND2") (pintype "bidirectional"))
      (node (ref "CN150") (pin "GND3") (pinfunction "SHIELD_GND3") (pintype "bidirectional"))
      (node (ref "CN150") (pin "GND4") (pinfunction "SHIELD_GND4") (pintype "bidirectional"))
      (node (ref "CN2") (pin "5") (pinfunction "5_5") (pintype "input"))
      (node (ref "CN2") (pin "M1") (pinfunction "S1_M1") (pintype "passive"))
      (node (ref "CN2") (pin "M2") (pinfunction "S2_M2") (pintype "passive"))
      (node (ref "CN2") (pin "M3") (pinfunction "S3_M3") (pintype "passive"))
      (node (ref "CN2") (pin "M4") (pinfunction "S4_M4") (pintype "passive"))
      (node (ref "D1") (pin "2") (pinfunction "A_2") (pintype "passive"))
      (node (ref "GND") (pin "1") (pinfunction "1_1") (pintype "passive"))
      (node (ref "HOLE1") (pin "GND") (pinfunction "GND-SCREW_GND") (pintype "bidirectional"))
      (node (ref "HOLE2") (pin "GND") (pinfunction "GND-SCREW_GND") (pintype "bidirectional"))
      (node (ref "HOLE3") (pin "GND") (pinfunction "GND-SCREW_GND") (pintype "bidirectional"))
      (node (ref "HOLE4") (pin "GND") (pinfunction "GND-SCREW_GND") (pintype "bidirectional"))
      (node (ref "IC1") (pin "31") (pinfunction "VSS1_31") (pintype "bidirectional"))
      (node (ref "IC1") (pin "41") (pinfunction "VSS2_41") (pintype "bidirectional"))
      (node (ref "IC1") (pin "55") (pinfunction "VSS3_55") (pintype "bidirectional"))
      (node (ref "IC1") (pin "72") (pinfunction "VSS4_72") (pintype "bidirectional"))
      (node (ref "IC1") (pin "83") (pinfunction "VSS6_83") (pintype "bidirectional"))
      (node (ref "IC1") (pin "97") (pinfunction "VSS5_97") (pintype "bidirectional"))
      (node (ref "IC2") (pin "2") (pinfunction "GND_2") (pintype "passive"))
      (node (ref "IC3") (pin "2") (pinfunction "GND_2") (pintype "passive"))
      (node (ref "LD0") (pin "C") (pinfunction "C_C") (pintype "passive"))
      (node (ref "LD1") (pin "C") (pinfunction "C_C") (pintype "passive"))
      (node (ref "LD2") (pin "C") (pinfunction "C_C") (pintype "passive"))
      (node (ref "LD3") (pin "C") (pinfunction "C_C") (pintype "passive"))
      (node (ref "LD4") (pin "C") (pinfunction "C_C") (pintype "passive"))
      (node (ref "P1") (pin "GNDMOT") (pinfunction "GNDMOT_GNDMOT") (pintype "power_in"))
      (node (ref "P1") (pin "GNDVDD") (pinfunction "GNDVDD_GNDVDD") (pintype "power_in"))
      (node (ref "P2") (pin "GNDMOT") (pinfunction "GNDMOT_GNDMOT") (pintype "power_in"))
      (node (ref "P2") (pin "GNDVDD") (pinfunction "GNDVDD_GNDVDD") (pintype "power_in"))
      (node (ref "P3") (pin "GNDMOT") (pinfunction "GNDMOT_GNDMOT") (pintype "power_in"))
      (node (ref "P3") (pin "GNDVDD") (pinfunction "GNDVDD_GNDVDD") (pintype "power_in"))
      (node (ref "P4") (pin "GNDMOT") (pinfunction "GNDMOT_GNDMOT") (pintype "power_in"))
      (node (ref "P4") (pin "GNDVDD") (pinfunction "GNDVDD_GNDVDD") (pintype "power_in"))
      (node (ref "P5") (pin "GNDMOT") (pinfunction "GNDMOT_GNDMOT") (pintype "power_in"))
      (node (ref "P5") (pin "GNDVDD") (pinfunction "GNDVDD_GNDVDD") (pintype "power_in"))
      (node (ref "Q1") (pin "1") (pinfunction "S_1") (pintype "passive"))
      (node (ref "Q1") (pin "2") (pinfunction "S_2") (pintype "passive"))
      (node (ref "Q1") (pin "3") (pinfunction "S_3") (pintype "passive"))
      (node (ref "Q2") (pin "1") (pinfunction "S_1") (pintype "passive"))
      (node (ref "Q2") (pin "2") (pinfunction "S_2") (pintype "passive"))
      (node (ref "Q2") (pin "3") (pinfunction "S_3") (pintype "passive"))
      (node (ref "Q3") (pin "1") (pinfunction "S_1") (pintype "passive"))
      (node (ref "Q3") (pin "2") (pinfunction "S_2") (pintype "passive"))
      (node (ref "Q3") (pin "3") (pinfunction "S_3") (pintype "passive"))
      (node (ref "Q4") (pin "2") (pinfunction "S_2") (pintype "passive"))
      (node (ref "R13") (pin "2") (pinfunction "2_2") (pintype "passive"))
      (node (ref "R14") (pin "2") (pinfunction "2_2") (pintype "passive"))
      (node (ref "R15") (pin "2") (pinfunction "2_2") (pintype "passive"))
      (node (ref "R16") (pin "2") (pinfunction "2_2") (pintype "passive"))
      (node (ref "R20") (pin "2") (pinfunction "2_2") (pintype "passive"))
      (node (ref "R21") (pin "2") (pinfunction "2_2") (pintype "passive"))
      (node (ref "R22") (pin "2") (pinfunction "2_2") (pintype "passive"))
      (node (ref "R23") (pin "2") (pinfunction "2_2") (pintype "passive"))
      (node (ref "R24") (pin "2") (pinfunction "2_2") (pintype "passive"))
      (node (ref "SW1") (pin "2") (pinfunction "S_2") (pintype "passive"))
      (node (ref "SW1") (pin "3") (pinfunction "S_3") (pintype "passive"))
      (node (ref "SW1") (pin "4") (pinfunction "S_4") (pintype "passive"))
      (node (ref "X1") (pin "2") (pinfunction "2_2") (pintype "passive"))
      (node (ref "X1") (pin "4") (pinfunction "4_4") (pintype "passive"))
    )
    (net (code "69") (name "Net-(C16-Pad1)") (class "Default")
      (node (ref "C16") (pin "1") (pinfunction "1_1") (pintype "passive"))
      (node (ref "CN2") (pin "2") (pinfunction "2_2") (pintype "input"))
      (node (ref "R1") (pin "2") (pinfunction "2_2") (pintype "passive"))
    )
    (net (code "70") (name "Net-(C17-Pad1)") (class "Default")
      (node (ref "C17") (pin "1") (pinfunction "1_1") (pintype "passive"))
      (node (ref "CN2") (pin "3") (pinfunction "3_3") (pintype "input"))
      (node (ref "R2") (pin "2") (pinfunction "2_2") (pintype "passive"))
      (node (ref "R3") (pin "2") (pinfunction "2_2") (pintype "passive"))
    )
    (net (code "71") (name "Net-(CN131-Pad5)") (class "Default")
      (node (ref "CN131") (pin "5") (pinfunction "5_5") (pintype "passive"))
      (node (ref "R9") (pin "1") (pinfunction "1_1") (pintype "passive"))
    )
    (net (code "72") (name "Net-(IC1-XTAL1)") (class "Default")
      (node (ref "C15") (pin "1") (pinfunction "1_1") (pintype "passive"))
      (node (ref "IC1") (pin "22") (pinfunction "XTAL1_22") (pintype "bidirectional"))
      (node (ref "X1") (pin "3") (pinfunction "3_3") (pintype "passive"))
    )
    (net (code "73") (name "Net-(IC1-XTAL2)") (class "Default")
      (node (ref "C14") (pin "1") (pinfunction "1_1") (pintype "passive"))
      (node (ref "IC1") (pin "23") (pinfunction "XTAL2_23") (pintype "bidirectional"))
      (node (ref "X1") (pin "1") (pinfunction "1_1") (pintype "passive"))
    )
    (net (code "74") (name "Net-(LD0-PadA)") (class "Default")
      (node (ref "LD0") (pin "A") (pinfunction "A_A") (pintype "passive"))
      (node (ref "R4") (pin "1") (pinfunction "1_1") (pintype "passive"))
    )
    (net (code "75") (name "Net-(LD1-PadA)") (class "Default")
      (node (ref "LD1") (pin "A") (pinfunction "A_A") (pintype "passive"))
      (node (ref "R5") (pin "1") (pinfunction "1_1") (pintype "passive"))
    )
    (net (code "76") (name "Net-(LD2-PadA)") (class "Default")
      (node (ref "LD2") (pin "A") (pinfunction "A_A") (pintype "passive"))
      (node (ref "R6") (pin "1") (pinfunction "1_1") (pintype "passive"))
    )
    (net (code "77") (name "Net-(LD3-PadA)") (class "Default")
      (node (ref "LD3") (pin "A") (pinfunction "A_A") (pintype "passive"))
      (node (ref "R7") (pin "1") (pinfunction "1_1") (pintype "passive"))
    )
    (net (code "78") (name "Net-(LD4-PadA)") (class "Default")
      (node (ref "LD4") (pin "A") (pinfunction "A_A") (pintype "passive"))
      (node (ref "R8") (pin "1") (pinfunction "1_1") (pintype "passive"))
    )
    (net (code "79") (name "Net-(P1-MOT-1A)") (class "Default")
      (node (ref "CN101") (pin "3") (pinfunction "3_3") (pintype "passive"))
      (node (ref "P1") (pin "1A") (pinfunction "MOT-1A_1A") (pintype "power_in"))
    )
    (net (code "80") (name "Net-(P1-MOT-1B)") (class "Default")
      (node (ref "CN101") (pin "4") (pinfunction "4_4") (pintype "passive"))
      (node (ref "P1") (pin "1B") (pinfunction "MOT-1B_1B") (pintype "power_in"))
    )
    (net (code "81") (name "Net-(P1-MOT-2A)") (class "Default")
      (node (ref "CN101") (pin "2") (pinfunction "2_2") (pintype "passive"))
      (node (ref "P1") (pin "2A") (pinfunction "MOT-2A_2A") (pintype "power_in"))
    )
    (net (code "82") (name "Net-(P1-MOT-2B)") (class "Default")
      (node (ref "CN101") (pin "1") (pinfunction "1_1") (pintype "passive"))
      (node (ref "P1") (pin "2B") (pinfunction "MOT-2B_2B") (pintype "power_in"))
    )
    (net (code "83") (name "Net-(P1-~{RESET})") (class "Default")
      (node (ref "P1") (pin "!RST") (pinfunction "~{RESET}_!RST") (pintype "input"))
      (node (ref "P1") (pin "!SLP") (pinfunction "~{SLEEP}_!SLP") (pintype "input"))
    )
    (net (code "84") (name "Net-(P2-MOT-1A)") (class "Default")
      (node (ref "CN102") (pin "3") (pinfunction "3_3") (pintype "passive"))
      (node (ref "P2") (pin "1A") (pinfunction "MOT-1A_1A") (pintype "power_in"))
    )
    (net (code "85") (name "Net-(P2-MOT-1B)") (class "Default")
      (node (ref "CN102") (pin "4") (pinfunction "4_4") (pintype "passive"))
      (node (ref "P2") (pin "1B") (pinfunction "MOT-1B_1B") (pintype "power_in"))
    )
    (net (code "86") (name "Net-(P2-MOT-2A)") (class "Default")
      (node (ref "CN102") (pin "2") (pinfunction "2_2") (pintype "passive"))
      (node (ref "P2") (pin "2A") (pinfunction "MOT-2A_2A") (pintype "power_in"))
    )
    (net (code "87") (name "Net-(P2-MOT-2B)") (class "Default")
      (node (ref "CN102") (pin "1") (pinfunction "1_1") (pintype "passive"))
      (node (ref "P2") (pin "2B") (pinfunction "MOT-2B_2B") (pintype "power_in"))
    )
    (net (code "88") (name "Net-(P2-~{RESET})") (class "Default")
      (node (ref "P2") (pin "!RST") (pinfunction "~{RESET}_!RST") (pintype "input"))
      (node (ref "P2") (pin "!SLP") (pinfunction "~{SLEEP}_!SLP") (pintype "input"))
    )
    (net (code "89") (name "Net-(P3-MOT-1A)") (class "Default")
      (node (ref "CN103") (pin "3") (pinfunction "3_3") (pintype "passive"))
      (node (ref "CN104") (pin "3") (pinfunction "3_3") (pintype "passive"))
      (node (ref "P3") (pin "1A") (pinfunction "MOT-1A_1A") (pintype "power_in"))
    )
    (net (code "90") (name "Net-(P3-MOT-1B)") (class "Default")
      (node (ref "CN103") (pin "4") (pinfunction "4_4") (pintype "passive"))
      (node (ref "CN104") (pin "4") (pinfunction "4_4") (pintype "passive"))
      (node (ref "P3") (pin "1B") (pinfunction "MOT-1B_1B") (pintype "power_in"))
    )
    (net (code "91") (name "Net-(P3-MOT-2A)") (class "Default")
      (node (ref "CN103") (pin "2") (pinfunction "2_2") (pintype "passive"))
      (node (ref "CN104") (pin "2") (pinfunction "2_2") (pintype "passive"))
      (node (ref "P3") (pin "2A") (pinfunction "MOT-2A_2A") (pintype "power_in"))
    )
    (net (code "92") (name "Net-(P3-MOT-2B)") (class "Default")
      (node (ref "CN103") (pin "1") (pinfunction "1_1") (pintype "passive"))
      (node (ref "CN104") (pin "1") (pinfunction "1_1") (pintype "passive"))
      (node (ref "P3") (pin "2B") (pinfunction "MOT-2B_2B") (pintype "power_in"))
    )
    (net (code "93") (name "Net-(P3-~{RESET})") (class "Default")
      (node (ref "P3") (pin "!RST") (pinfunction "~{RESET}_!RST") (pintype "input"))
      (node (ref "P3") (pin "!SLP") (pinfunction "~{SLEEP}_!SLP") (pintype "input"))
    )
    (net (code "94") (name "Net-(P4-MOT-1A)") (class "Default")
      (node (ref "CN105") (pin "3") (pinfunction "3_3") (pintype "passive"))
      (node (ref "P4") (pin "1A") (pinfunction "MOT-1A_1A") (pintype "power_in"))
    )
    (net (code "95") (name "Net-(P4-MOT-1B)") (class "Default")
      (node (ref "CN105") (pin "4") (pinfunction "4_4") (pintype "passive"))
      (node (ref "P4") (pin "1B") (pinfunction "MOT-1B_1B") (pintype "power_in"))
    )
    (net (code "96") (name "Net-(P4-MOT-2A)") (class "Default")
      (node (ref "CN105") (pin "2") (pinfunction "2_2") (pintype "passive"))
      (node (ref "P4") (pin "2A") (pinfunction "MOT-2A_2A") (pintype "power_in"))
    )
    (net (code "97") (name "Net-(P4-MOT-2B)") (class "Default")
      (node (ref "CN105") (pin "1") (pinfunction "1_1") (pintype "passive"))
      (node (ref "P4") (pin "2B") (pinfunction "MOT-2B_2B") (pintype "power_in"))
    )
    (net (code "98") (name "Net-(P4-~{RESET})") (class "Default")
      (node (ref "P4") (pin "!RST") (pinfunction "~{RESET}_!RST") (pintype "input"))
      (node (ref "P4") (pin "!SLP") (pinfunction "~{SLEEP}_!SLP") (pintype "input"))
    )
    (net (code "99") (name "Net-(P5-MOT-1A)") (class "Default")
      (node (ref "CN106") (pin "3") (pinfunction "3_3") (pintype "passive"))
      (node (ref "P5") (pin "1A") (pinfunction "MOT-1A_1A") (pintype "power_in"))
    )
    (net (code "100") (name "Net-(P5-MOT-1B)") (class "Default")
      (node (ref "CN106") (pin "4") (pinfunction "4_4") (pintype "passive"))
      (node (ref "P5") (pin "1B") (pinfunction "MOT-1B_1B") (pintype "power_in"))
    )
    (net (code "101") (name "Net-(P5-MOT-2A)") (class "Default")
      (node (ref "CN106") (pin "2") (pinfunction "2_2") (pintype "passive"))
      (node (ref "P5") (pin "2A") (pinfunction "MOT-2A_2A") (pintype "power_in"))
    )
    (net (code "102") (name "Net-(P5-MOT-2B)") (class "Default")
      (node (ref "CN106") (pin "1") (pinfunction "1_1") (pintype "passive"))
      (node (ref "P5") (pin "2B") (pinfunction "MOT-2B_2B") (pintype "power_in"))
    )
    (net (code "103") (name "Net-(P5-~{RESET})") (class "Default")
      (node (ref "P5") (pin "!RST") (pinfunction "~{RESET}_!RST") (pintype "input"))
      (node (ref "P5") (pin "!SLP") (pinfunction "~{SLEEP}_!SLP") (pintype "input"))
    )
    (net (code "104") (name "Net-(Q1-D)") (class "Default")
      (node (ref "HOTEND0") (pin "1") (pinfunction "1_1") (pintype "passive"))
      (node (ref "Q1") (pin "MB") (pinfunction "D_MB") (pintype "passive"))
    )
    (net (code "105") (name "Net-(Q1-G)") (class "Default")
      (node (ref "Q1") (pin "4") (pinfunction "G_4") (pintype "passive"))
      (node (ref "R14") (pin "1") (pinfunction "1_1") (pintype "passive"))
      (node (ref "R26") (pin "2") (pinfunction "2_2") (pintype "passive"))
    )
    (net (code "106") (name "Net-(Q2-D)") (class "Default")
      (node (ref "HOTEND1") (pin "1") (pinfunction "1_1") (pintype "passive"))
      (node (ref "Q2") (pin "MB") (pinfunction "D_MB") (pintype "passive"))
    )
    (net (code "107") (name "Net-(Q2-G)") (class "Default")
      (node (ref "Q2") (pin "4") (pinfunction "G_4") (pintype "passive"))
      (node (ref "R15") (pin "1") (pinfunction "1_1") (pintype "passive"))
      (node (ref "R27") (pin "2") (pinfunction "2_2") (pintype "passive"))
    )
    (net (code "108") (name "Net-(Q3-D)") (class "Default")
      (node (ref "HEATBED") (pin "1") (pinfunction "1_1") (pintype "passive"))
      (node (ref "Q3") (pin "MB") (pinfunction "D_MB") (pintype "passive"))
    )
    (net (code "109") (name "Net-(Q3-G)") (class "Default")
      (node (ref "Q3") (pin "4") (pinfunction "G_4") (pintype "passive"))
      (node (ref "R16") (pin "1") (pinfunction "1_1") (pintype "passive"))
      (node (ref "R28") (pin "2") (pinfunction "2_2") (pintype "passive"))
    )
    (net (code "110") (name "Net-(Q4-D)") (class "Default")
      (node (ref "FAN") (pin "1") (pinfunction "1_1") (pintype "passive"))
      (node (ref "Q4") (pin "3") (pinfunction "D_3") (pintype "passive"))
    )
    (net (code "111") (name "Net-(Q4-G)") (class "Default")
      (node (ref "Q4") (pin "1") (pinfunction "G_1") (pintype "passive"))
      (node (ref "R13") (pin "1") (pinfunction "1_1") (pintype "passive"))
      (node (ref "R25") (pin "2") (pinfunction "2_2") (pintype "passive"))
    )
    (net (code "112") (name "Net-(Q5-D)") (class "Default")
      (node (ref "Q5") (pin "3") (pinfunction "D_3") (pintype "passive"))
      (node (ref "R3") (pin "1") (pinfunction "1_1") (pintype "passive"))
    )
    (net (code "113") (name "unconnected-(CN2-Pad1)") (class "Default")
      (node (ref "CN2") (pin "1") (pinfunction "1_1") (pintype "input"))
    )
    (net (code "114") (name "unconnected-(CN2-Pad4)") (class "Default")
      (node (ref "CN2") (pin "4") (pinfunction "4_4") (pintype "input"))
    )
    (net (code "115") (name "unconnected-(CN150-NC-Pad1)") (class "Default")
      (node (ref "CN150") (pin "1") (pinfunction "NC_1") (pintype "bidirectional"))
    )
    (net (code "116") (name "unconnected-(CN150-NC-Pad8)") (class "Default")
      (node (ref "CN150") (pin "8") (pinfunction "NC_8") (pintype "bidirectional"))
    )
    (net (code "117") (name "unconnected-(CN150-PadCD1)") (class "Default")
      (node (ref "CN150") (pin "CD1") (pinfunction "CD1_CD1") (pintype "bidirectional"))
    )
    (net (code "118") (name "unconnected-(CN150-PadCD2)") (class "Default")
      (node (ref "CN150") (pin "CD2") (pinfunction "CD2_CD2") (pintype "bidirectional"))
    )
    (net (code "119") (name "unconnected-(IC1-NC-Pad13)") (class "Default")
      (node (ref "IC1") (pin "13") (pinfunction "NC_13") (pintype "bidirectional"))
    )
    (net (code "120") (name "unconnected-(IC1-P1[0]{slash}ENET_TXD0-Pad95)") (class "Default")
      (node (ref "IC1") (pin "95") (pinfunction "P1[0]/ENET_TXD0_95") (pintype "bidirectional"))
    )
    (net (code "121") (name "unconnected-(IC1-P1[1]{slash}ENET_TXD1-Pad94)") (class "Default")
      (node (ref "IC1") (pin "94") (pinfunction "P1[1]/ENET_TXD1_94") (pintype "bidirectional"))
    )
    (net (code "122") (name "unconnected-(IC1-P1[4]{slash}ENET_TX_EN-Pad93)") (class "Default")
      (node (ref "IC1") (pin "93") (pinfunction "P1[4]/ENET_TX_EN_93") (pintype "bidirectional"))
    )
    (net (code "123") (name "unconnected-(IC1-P1[8]{slash}ENET_CRS-Pad92)") (class "Default")
      (node (ref "IC1") (pin "92") (pinfunction "P1[8]/ENET_CRS_92") (pintype "bidirectional"))
    )
    (net (code "124") (name "unconnected-(IC1-P1[9]{slash}ENET_RXD0-Pad91)") (class "Default")
      (node (ref "IC1") (pin "91") (pinfunction "P1[9]/ENET_RXD0_91") (pintype "bidirectional"))
    )
    (net (code "125") (name "unconnected-(IC1-P1[10]{slash}ENET_RXD1-Pad90)") (class "Default")
      (node (ref "IC1") (pin "90") (pinfunction "P1[10]/ENET_RXD1_90") (pintype "bidirectional"))
    )
    (net (code "126") (name "unconnected-(IC1-P1[14]{slash}ENET_RX_ER-Pad89)") (class "Default")
      (node (ref "IC1") (pin "89") (pinfunction "P1[14]/ENET_RX_ER_89") (pintype "bidirectional"))
    )
    (net (code "127") (name "unconnected-(IC1-P1[15]{slash}ENET_REF_CLK-Pad88)") (class "Default")
      (node (ref "IC1") (pin "88") (pinfunction "P1[15]/ENET_REF_CLK_88") (pintype "bidirectional"))
    )
    (net (code "128") (name "unconnected-(IC1-P1[16]{slash}ENET_MDC-Pad87)") (class "Default")
      (node (ref "IC1") (pin "87") (pinfunction "P1[16]/ENET_MDC_87") (pintype "bidirectional"))
    )
    (net (code "129") (name "unconnected-(IC1-P1[17]{slash}ENET_MDIO-Pad86)") (class "Default")
      (node (ref "IC1") (pin "86") (pinfunction "P1[17]/ENET_MDIO_86") (pintype "bidirectional"))
    )
    (net (code "130") (name "unconnected-(IC1-RTCK-Pad100)") (class "Default")
      (node (ref "IC1") (pin "100") (pinfunction "RTCK_100") (pintype "bidirectional"))
    )
    (net (code "131") (name "unconnected-(IC1-RTCX1-Pad16)") (class "Default")
      (node (ref "IC1") (pin "16") (pinfunction "RTCX1_16") (pintype "bidirectional"))
    )
    (net (code "132") (name "unconnected-(IC1-RTCX2-Pad18)") (class "Default")
      (node (ref "IC1") (pin "18") (pinfunction "RTCX2_18") (pintype "bidirectional"))
    )
    (net (code "133") (name "unconnected-(IC1-TCK{slash}SWDCLK-Pad5)") (class "Default")
      (node (ref "IC1") (pin "5") (pinfunction "TCK/SWDCLK_5") (pintype "bidirectional"))
    )
    (net (code "134") (name "unconnected-(IC1-TDI-Pad2)") (class "Default")
      (node (ref "IC1") (pin "2") (pinfunction "TDI_2") (pintype "bidirectional"))
    )
    (net (code "135") (name "unconnected-(IC1-TDO{slash}SWO-Pad1)") (class "Default")
      (node (ref "IC1") (pin "1") (pinfunction "TDO/SWO_1") (pintype "bidirectional"))
    )
    (net (code "136") (name "unconnected-(IC1-TMS{slash}SWDIO-Pad3)") (class "Default")
      (node (ref "IC1") (pin "3") (pinfunction "TMS/SWDIO_3") (pintype "bidirectional"))
    )
    (net (code "137") (name "unconnected-(IC1-~{RSTOUT}-Pad14)") (class "Default")
      (node (ref "IC1") (pin "14") (pinfunction "~{RSTOUT}_14") (pintype "bidirectional"))
    )
    (net (code "138") (name "unconnected-(IC1-~{TRST}-Pad4)") (class "Default")
      (node (ref "IC1") (pin "4") (pinfunction "~{TRST}_4") (pintype "bidirectional"))
    )
  )
)
